# plugV6-Relay-NC-4.net
KiCad netlist of a schematic drawn in EAGLE
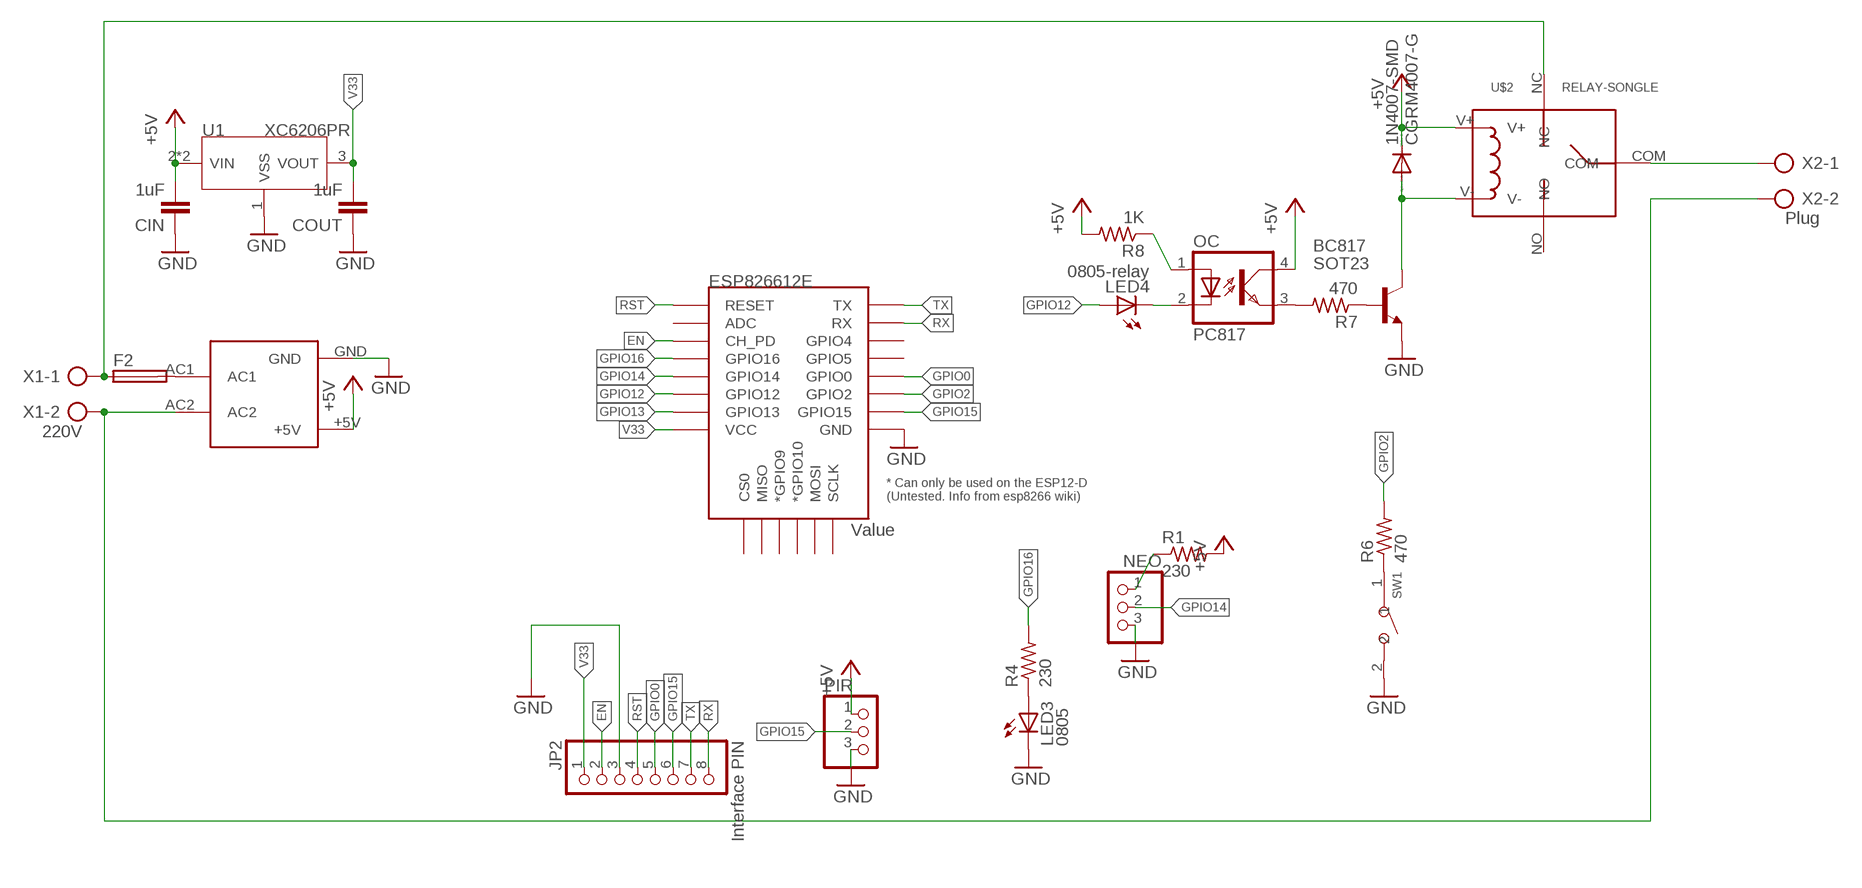
[diagram p0: schematic, sheet 1]

(export (version "E")
  (design (tool "Eeschema 10.0.6"))
  (components
    (comp (ref "1N4007-SMD")
      (value "CGRM4007-G")
      (footprint "eagle-import:SOD-123_MINI-SMA")
      (libsource (lib "eagle-import") (part "CGRM400-G7"))
    )
    (comp (ref "BC817")
      (value "SOT23")
      (footprint "eagle-import:SOT23-BEC")
      (libsource (lib "eagle-import") (part "-NPN-SOT23-BECBC817"))
    )
    (comp (ref "CIN")
      (value "1uF")
      (footprint "eagle-import:C0805")
      (libsource (lib "eagle-import") (part "C-EUC0805"))
    )
    (comp (ref "COUT")
      (value "1uF")
      (footprint "eagle-import:C0805")
      (libsource (lib "eagle-import") (part "C-EUC0805"))
    )
    (comp (ref "ESP826612E")
      (value "Value")
      (footprint "eagle-import:ESP12E-SMD")
      (libsource (lib "eagle-import") (part "ESP12ESMD"))
    )
    (comp (ref "F2")
      (value "TR5")
      (footprint "eagle-import:TR5")
      (libsource (lib "eagle-import") (part "TR5"))
    )
    (comp (ref "JP2")
      (value "Interface PIN")
      (footprint "eagle-import:1X08")
      (libsource (lib "eagle-import") (part "PINHD-1X8"))
    )
    (comp (ref "LED3")
      (value "0805")
      (footprint "eagle-import:CHIP-LED0603")
      (libsource (lib "eagle-import") (part "LEDCHIP-LED0603"))
    )
    (comp (ref "LED4")
      (value "0805-relay")
      (footprint "eagle-import:CHIP-LED0603")
      (libsource (lib "eagle-import") (part "LEDCHIP-LED0603"))
    )
    (comp (ref "NEO")
      (value "PINHD-1X3")
      (footprint "eagle-import:1X03")
      (libsource (lib "eagle-import") (part "PINHD-1X3"))
    )
    (comp (ref "OC")
      (value "PC817")
      (footprint "eagle-import:DIL04")
      (fields (field (name "MPN") "PC817X4J000F"))
      (libsource (lib "eagle-import") (part "PC817"))
    )
    (comp (ref "PIR")
      (value "PINHD-1X3")
      (footprint "eagle-import:1X03")
      (libsource (lib "eagle-import") (part "PINHD-1X3"))
    )
    (comp (ref "R1")
      (value "230")
      (footprint "eagle-import:R1206")
      (libsource (lib "eagle-import") (part "R-US_R1206"))
    )
    (comp (ref "R4")
      (value "230")
      (footprint "eagle-import:R1206")
      (libsource (lib "eagle-import") (part "R-US_R1206"))
    )
    (comp (ref "R6")
      (value "470")
      (footprint "eagle-import:R1206")
      (libsource (lib "eagle-import") (part "R-US_R1206"))
    )
    (comp (ref "R7")
      (value "470")
      (footprint "eagle-import:R1206")
      (libsource (lib "eagle-import") (part "R-US_R1206"))
    )
    (comp (ref "R8")
      (value "1K")
      (footprint "eagle-import:R1206")
      (libsource (lib "eagle-import") (part "R-US_R1206"))
    )
    (comp (ref "SW1")
      (value "DIP-BUTTON(2P-6.0X3.0X4.3MM)-TS-1101F")
      (footprint "eagle-import:SW2-5.0-6.0X3.0X4.3MM")
      (libsource (lib "eagle-import") (part "DIP-BUTTON(2P-6.0X3.0X4.3MM)-TS-1101F"))
    )
    (comp (ref "U$1")
      (value "HLK-PM01")
      (footprint "eagle-import:HLK-PM01")
      (libsource (lib "eagle-import") (part "HLK-PM01"))
    )
    (comp (ref "U$2")
      (value "RELAY-SONGLE")
      (footprint "eagle-import:RELAY-SONGLE")
      (libsource (lib "eagle-import") (part "RELAY-SONGLE"))
    )
    (comp (ref "U1")
      (value "XC6206PR")
      (footprint "eagle-import:SOT89")
      (libsource (lib "eagle-import") (part "XC6206PR"))
    )
    (comp (ref "X1")
      (value "220V")
      (footprint "eagle-import:AK300_2")
      (libsource (lib "eagle-import") (part "AK300/2"))
    )
    (comp (ref "X2")
      (value "Plug")
      (footprint "eagle-import:AK300_2")
      (libsource (lib "eagle-import") (part "AK300/2"))
    )
  )
  (nets
    (net (code "1") (name "+5V") (class "Default")
      (node (ref "1N4007-SMD") (pin "C") (pinfunction "C_C") (pintype "passive"))
      (node (ref "CIN") (pin "2") (pinfunction "2_2") (pintype "passive"))
      (node (ref "OC") (pin "4") (pinfunction "COL_4") (pintype "passive"))
      (node (ref "PIR") (pin "1") (pinfunction "1_1") (pintype "passive"))
      (node (ref "R1") (pin "2") (pinfunction "2_2") (pintype "passive"))
      (node (ref "R8") (pin "2") (pinfunction "2_2") (pintype "passive"))
      (node (ref "U$1") (pin "+5V") (pinfunction "+5V_+5V") (pintype "bidirectional"))
      (node (ref "U$2") (pin "V+") (pinfunction "V+_V+") (pintype "bidirectional"))
      (node (ref "U1") (pin "2") (pinfunction "VIN_2") (pintype "input"))
      (node (ref "U1") (pin "4") (pinfunction "VIN_4") (pintype "input"))
    )
    (net (code "2") (name "EN") (class "Default")
      (node (ref "ESP826612E") (pin "CH_PD") (pinfunction "CH_PD_CH_PD") (pintype "bidirectional"))
      (node (ref "JP2") (pin "2") (pinfunction "2_2") (pintype "passive"))
    )
    (net (code "3") (name "GND") (class "Default")
      (node (ref "BC817") (pin "E") (pinfunction "E_E") (pintype "passive"))
      (node (ref "CIN") (pin "1") (pinfunction "1_1") (pintype "passive"))
      (node (ref "COUT") (pin "1") (pinfunction "1_1") (pintype "passive"))
      (node (ref "ESP826612E") (pin "GND") (pinfunction "GND_GND") (pintype "bidirectional"))
      (node (ref "JP2") (pin "3") (pinfunction "3_3") (pintype "passive"))
      (node (ref "LED3") (pin "C") (pinfunction "C_C") (pintype "passive"))
      (node (ref "NEO") (pin "3") (pinfunction "3_3") (pintype "passive"))
      (node (ref "PIR") (pin "3") (pinfunction "3_3") (pintype "passive"))
      (node (ref "SW1") (pin "2") (pinfunction "2_2") (pintype "bidirectional"))
      (node (ref "U$1") (pin "GND") (pinfunction "GND_GND") (pintype "bidirectional"))
      (node (ref "U1") (pin "1") (pinfunction "VSS_1") (pintype "power_in"))
    )
    (net (code "4") (name "GPIO0") (class "Default")
      (node (ref "ESP826612E") (pin "GPIO0") (pinfunction "GPIO0_GPIO0") (pintype "bidirectional"))
      (node (ref "JP2") (pin "5") (pinfunction "5_5") (pintype "passive"))
    )
    (net (code "5") (name "GPIO2") (class "Default")
      (node (ref "ESP826612E") (pin "GPIO2") (pinfunction "GPIO2_GPIO2") (pintype "bidirectional"))
      (node (ref "R6") (pin "2") (pinfunction "2_2") (pintype "passive"))
    )
    (net (code "6") (name "GPIO12") (class "Default")
      (node (ref "ESP826612E") (pin "GPIO12") (pinfunction "GPIO12_GPIO12") (pintype "bidirectional"))
      (node (ref "LED4") (pin "A") (pinfunction "A_A") (pintype "passive"))
    )
    (net (code "7") (name "GPIO13") (class "Default")
      (node (ref "ESP826612E") (pin "GPIO13") (pinfunction "GPIO13_GPIO13") (pintype "bidirectional"))
    )
    (net (code "8") (name "GPIO14") (class "Default")
      (node (ref "ESP826612E") (pin "GPIO14") (pinfunction "GPIO14_GPIO14") (pintype "bidirectional"))
      (node (ref "NEO") (pin "2") (pinfunction "2_2") (pintype "passive"))
    )
    (net (code "9") (name "GPIO15") (class "Default")
      (node (ref "ESP826612E") (pin "GPIO15") (pinfunction "GPIO15_GPIO15") (pintype "bidirectional"))
      (node (ref "JP2") (pin "6") (pinfunction "6_6") (pintype "passive"))
      (node (ref "PIR") (pin "2") (pinfunction "2_2") (pintype "passive"))
    )
    (net (code "10") (name "GPIO16") (class "Default")
      (node (ref "ESP826612E") (pin "GPIO16") (pinfunction "GPIO16_GPIO16") (pintype "bidirectional"))
      (node (ref "R4") (pin "2") (pinfunction "2_2") (pintype "passive"))
    )
    (net (code "11") (name "Net-(1N4007-SMD-PadA)") (class "Default")
      (node (ref "1N4007-SMD") (pin "A") (pinfunction "A_A") (pintype "passive"))
      (node (ref "BC817") (pin "C") (pinfunction "C_C") (pintype "passive"))
      (node (ref "U$2") (pin "V-") (pinfunction "V-_V-") (pintype "bidirectional"))
    )
    (net (code "12") (name "Net-(BC817-PadB)") (class "Default")
      (node (ref "BC817") (pin "B") (pinfunction "B_B") (pintype "passive"))
      (node (ref "R7") (pin "1") (pinfunction "1_1") (pintype "passive"))
    )
    (net (code "13") (name "Net-(F2-Pad2)") (class "Default")
      (node (ref "F2") (pin "2") (pinfunction "2_2") (pintype "passive"))
      (node (ref "U$1") (pin "AC1") (pinfunction "AC1_AC1") (pintype "bidirectional"))
    )
    (net (code "14") (name "Net-(LED3-PadA)") (class "Default")
      (node (ref "LED3") (pin "A") (pinfunction "A_A") (pintype "passive"))
      (node (ref "R4") (pin "1") (pinfunction "1_1") (pintype "passive"))
    )
    (net (code "15") (name "Net-(NEO-Pad1)") (class "Default")
      (node (ref "NEO") (pin "1") (pinfunction "1_1") (pintype "passive"))
      (node (ref "R1") (pin "1") (pinfunction "1_1") (pintype "passive"))
    )
    (net (code "16") (name "Net-(OC-A)") (class "Default")
      (node (ref "OC") (pin "1") (pinfunction "A_1") (pintype "passive"))
      (node (ref "R8") (pin "1") (pinfunction "1_1") (pintype "passive"))
    )
    (net (code "17") (name "Net-(OC-C)") (class "Default")
      (node (ref "LED4") (pin "C") (pinfunction "C_C") (pintype "passive"))
      (node (ref "OC") (pin "2") (pinfunction "C_2") (pintype "passive"))
    )
    (net (code "18") (name "Net-(OC-EMIT)") (class "Default")
      (node (ref "OC") (pin "3") (pinfunction "EMIT_3") (pintype "passive"))
      (node (ref "R7") (pin "2") (pinfunction "2_2") (pintype "passive"))
    )
    (net (code "19") (name "Net-(R6-Pad1)") (class "Default")
      (node (ref "R6") (pin "1") (pinfunction "1_1") (pintype "passive"))
      (node (ref "SW1") (pin "1") (pinfunction "1_1") (pintype "bidirectional"))
    )
    (net (code "20") (name "Net-(X1A-KL)") (class "Default")
      (node (ref "F2") (pin "1") (pinfunction "1_1") (pintype "passive"))
      (node (ref "U$2") (pin "NC") (pinfunction "NC_NC") (pintype "bidirectional"))
      (node (ref "X1") (pin "1") (pinfunction "KL_1") (pintype "passive"))
    )
    (net (code "21") (name "Net-(X1B-KL)") (class "Default")
      (node (ref "U$1") (pin "AC2") (pinfunction "AC2_AC2") (pintype "bidirectional"))
      (node (ref "X1") (pin "2") (pinfunction "KL_2") (pintype "passive"))
      (node (ref "X2") (pin "2") (pinfunction "KL_2") (pintype "passive"))
    )
    (net (code "22") (name "Net-(X2A-KL)") (class "Default")
      (node (ref "U$2") (pin "COM") (pinfunction "COM_COM") (pintype "bidirectional"))
      (node (ref "X2") (pin "1") (pinfunction "KL_1") (pintype "passive"))
    )
    (net (code "23") (name "RST") (class "Default")
      (node (ref "ESP826612E") (pin "RESET") (pinfunction "RESET_RESET") (pintype "bidirectional"))
      (node (ref "JP2") (pin "4") (pinfunction "4_4") (pintype "passive"))
    )
    (net (code "24") (name "RX") (class "Default")
      (node (ref "ESP826612E") (pin "RXD0") (pinfunction "RX_RXD0") (pintype "bidirectional"))
      (node (ref "JP2") (pin "8") (pinfunction "8_8") (pintype "passive"))
    )
    (net (code "25") (name "TX") (class "Default")
      (node (ref "ESP826612E") (pin "TXD0") (pinfunction "TX_TXD0") (pintype "bidirectional"))
      (node (ref "JP2") (pin "7") (pinfunction "7_7") (pintype "passive"))
    )
    (net (code "26") (name "V33") (class "Default")
      (node (ref "COUT") (pin "2") (pinfunction "2_2") (pintype "passive"))
      (node (ref "ESP826612E") (pin "VCC") (pinfunction "VCC_VCC") (pintype "bidirectional"))
      (node (ref "JP2") (pin "1") (pinfunction "1_1") (pintype "passive"))
      (node (ref "U1") (pin "3") (pinfunction "VOUT_3") (pintype "output"))
    )
    (net (code "27") (name "unconnected-(ESP826612E-*GPIO9-PadGPIO9)") (class "Default")
      (node (ref "ESP826612E") (pin "GPIO9") (pinfunction "*GPIO9_GPIO9") (pintype "bidirectional"))
    )
    (net (code "28") (name "unconnected-(ESP826612E-*GPIO10-PadGPIO10)") (class "Default")
      (node (ref "ESP826612E") (pin "GPIO10") (pinfunction "*GPIO10_GPIO10") (pintype "bidirectional"))
    )
    (net (code "29") (name "unconnected-(ESP826612E-PadADC)") (class "Default")
      (node (ref "ESP826612E") (pin "ADC") (pinfunction "ADC_ADC") (pintype "bidirectional"))
    )
    (net (code "30") (name "unconnected-(ESP826612E-PadCS0)") (class "Default")
      (node (ref "ESP826612E") (pin "CS0") (pinfunction "CS0_CS0") (pintype "bidirectional"))
    )
    (net (code "31") (name "unconnected-(ESP826612E-PadGPIO4)") (class "Default")
      (node (ref "ESP826612E") (pin "GPIO4") (pinfunction "GPIO4_GPIO4") (pintype "bidirectional"))
    )
    (net (code "32") (name "unconnected-(ESP826612E-PadGPIO5)") (class "Default")
      (node (ref "ESP826612E") (pin "GPIO5") (pinfunction "GPIO5_GPIO5") (pintype "bidirectional"))
    )
    (net (code "33") (name "unconnected-(ESP826612E-PadMISO)") (class "Default")
      (node (ref "ESP826612E") (pin "MISO") (pinfunction "MISO_MISO") (pintype "bidirectional"))
    )
    (net (code "34") (name "unconnected-(ESP826612E-PadMOSI)") (class "Default")
      (node (ref "ESP826612E") (pin "MOSI") (pinfunction "MOSI_MOSI") (pintype "bidirectional"))
    )
    (net (code "35") (name "unconnected-(ESP826612E-PadSCLK)") (class "Default")
      (node (ref "ESP826612E") (pin "SCLK") (pinfunction "SCLK_SCLK") (pintype "bidirectional"))
    )
    (net (code "36") (name "unconnected-(U$2-PadNO)") (class "Default")
      (node (ref "U$2") (pin "NO") (pinfunction "NO_NO") (pintype "bidirectional"))
    )
  )
)
